# Sheet_2.net
KiCad netlist of a schematic drawn in Altium Designer
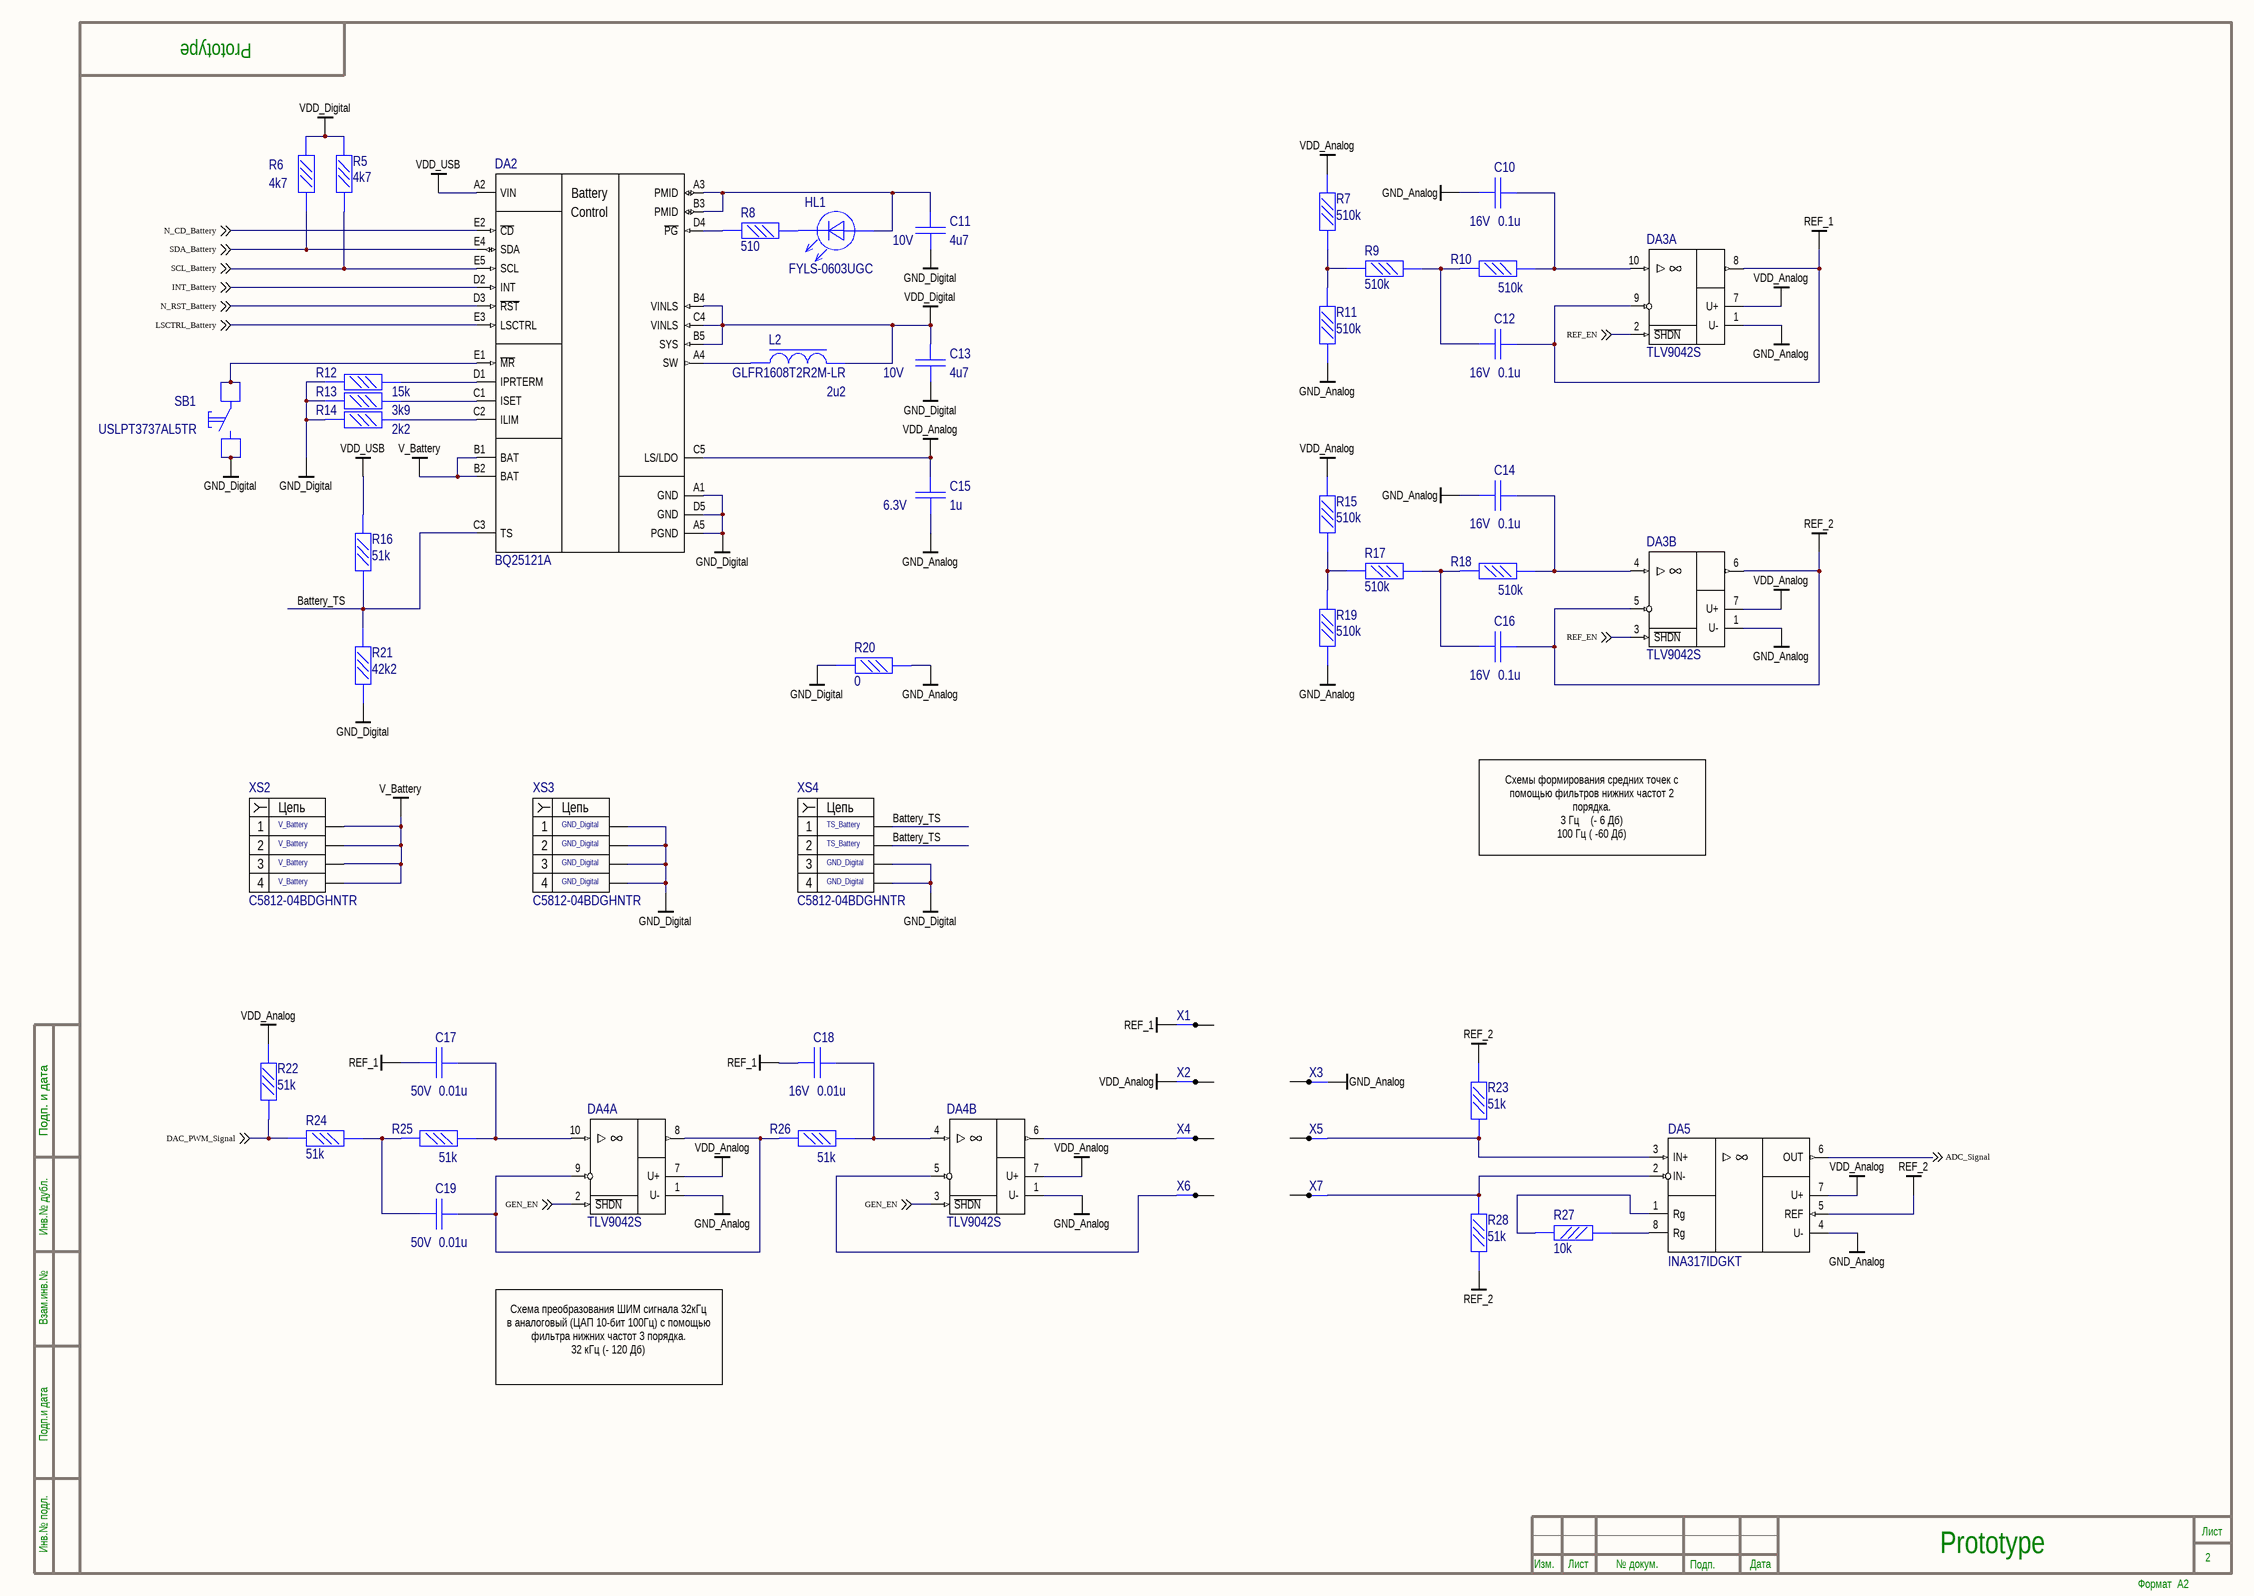
[diagram p0: Sheet_2.SchDoc]

(export (version "E")
  (design (tool "Eeschema 10.0.6"))
  (components
    (comp (ref "C10")
      (value "0.1u")
      (footprint "C0201_2")
      (fields
        (field (name "VOLTAGE") "16V")
        (field (name "Comment") "X7R")
        (field (name "PUBLISHER") "Andrew Danich")
      )
      (libsource (lib "Capacitor GOST") (part "X7R C0201"))
    )
    (comp (ref "C11")
      (value "4u7")
      (footprint "SMD Capacitor:C0603")
      (fields
        (field (name "VOLTAGE") "10V")
        (field (name "Comment") "X7R")
        (field (name "PUBLISHER") "Andrew Danich")
      )
      (libsource (lib "Capacitor GOST") (part "X7R C0603"))
    )
    (comp (ref "C12")
      (value "0.1u")
      (footprint "C0201_2")
      (fields
        (field (name "VOLTAGE") "16V")
        (field (name "Comment") "X7R")
        (field (name "PUBLISHER") "Andrew Danich")
      )
      (libsource (lib "Capacitor GOST") (part "X7R C0201"))
    )
    (comp (ref "C13")
      (value "4u7")
      (footprint "SMD Capacitor:C0603")
      (fields
        (field (name "VOLTAGE") "10V")
        (field (name "Comment") "X7R")
        (field (name "PUBLISHER") "Andrew Danich")
      )
      (libsource (lib "Capacitor GOST") (part "X7R C0603"))
    )
    (comp (ref "C14")
      (value "0.1u")
      (footprint "C0201_2")
      (fields
        (field (name "VOLTAGE") "16V")
        (field (name "Comment") "X7R")
        (field (name "PUBLISHER") "Andrew Danich")
      )
      (libsource (lib "Capacitor GOST") (part "X7R C0201"))
    )
    (comp (ref "C15")
      (value "1u")
      (footprint "SMD Capacitor:C0402")
      (fields
        (field (name "VOLTAGE") "6.3V")
        (field (name "Comment") "X5R")
        (field (name "PUBLISHER") "Andrew Danich")
      )
      (libsource (lib "Capacitor GOST") (part "X5R C0402"))
    )
    (comp (ref "C16")
      (value "0.1u")
      (footprint "C0201_2")
      (fields
        (field (name "VOLTAGE") "16V")
        (field (name "Comment") "X7R")
        (field (name "PUBLISHER") "Andrew Danich")
      )
      (libsource (lib "Capacitor GOST") (part "X7R C0201"))
    )
    (comp (ref "C17")
      (value "0.01u")
      (footprint "C0201_2")
      (fields
        (field (name "VOLTAGE") "50V")
        (field (name "Comment") "X7R")
        (field (name "PUBLISHER") "Andrew Danich")
      )
      (libsource (lib "Capacitor GOST") (part "X7R C0201"))
    )
    (comp (ref "C18")
      (value "0.01u")
      (footprint "C0201_2")
      (fields
        (field (name "VOLTAGE") "16V")
        (field (name "Comment") "X7R")
        (field (name "PUBLISHER") "Andrew Danich")
      )
      (libsource (lib "Capacitor GOST") (part "X7R C0201"))
    )
    (comp (ref "C19")
      (value "0.01u")
      (footprint "C0201_2")
      (fields
        (field (name "VOLTAGE") "50V")
        (field (name "Comment") "X7R")
        (field (name "PUBLISHER") "Andrew Danich")
      )
      (libsource (lib "Capacitor GOST") (part "X7R C0201"))
    )
    (comp (ref "DA2")
      (value "BQ25121A")
      (footprint "SMD WLCSP:dsbga-25")
      (fields (field (name "PUBLISHER") "Andrew Danich"))
      (libsource (lib "Battery Control GOST") (part "BQ25121A"))
    )
    (comp (ref "DA3")
      (value "TLV9042S")
      (footprint "SMD XDFN:X2QFN")
      (fields (field (name "Comment") "TLV9042SIRUGR") (field (name "PUBLISHER") "Andrew Danich"))
      (libsource (lib "OPA GOST") (part "TLV9042SIRUGR"))
    )
    (comp (ref "DA4")
      (value "TLV9042S")
      (footprint "SMD XDFN:X2QFN")
      (fields (field (name "Comment") "TLV9042SIRUGR") (field (name "PUBLISHER") "Andrew Danich"))
      (libsource (lib "OPA GOST") (part "TLV9042SIRUGR"))
    )
    (comp (ref "DA5")
      (value "INA317IDGKT")
      (footprint "SMD VSSOP:VSSOP-8")
      (fields (field (name "PUBLISHER") "Andrew Danich"))
      (libsource (lib "OPA GOST") (part "INA317IDGKT"))
    )
    (comp (ref "HL1")
      (value "FYLS-0603UGC")
      (footprint "SMD Leds:LD0603")
      (fields (field (name "PUBLISHER") "Andrew Danich"))
      (libsource (lib "Led GOST") (part "FYLS-0603UGC"))
    )
    (comp (ref "L2")
      (value "2u2")
      (footprint "SMD Coil:L0603")
      (fields
        (field (name "NAME") "GLFR1608T2R2M-LR")
        (field (name "Comment") "GLFR1608T2R2M-LR")
        (field (name "PUBLISHER") "Andrew Danich")
      )
      (libsource (lib "Coil GOST") (part "GLFR1608T2R2M-LR"))
    )
    (comp (ref "R5")
      (value "4k7")
      (footprint "R0201_2")
      (fields (field (name "Comment") "ERJ1GN") (field (name "PUBLISHER") "Andrew Danich"))
      (libsource (lib "Resistor GOST") (part "R0201"))
    )
    (comp (ref "R6")
      (value "4k7")
      (footprint "R0201_2")
      (fields (field (name "Comment") "ERJ1GN") (field (name "PUBLISHER") "Andrew Danich"))
      (libsource (lib "Resistor GOST") (part "R0201"))
    )
    (comp (ref "R7")
      (value "510k")
      (footprint "R0201_2")
      (fields (field (name "Comment") "ERJ1GN") (field (name "PUBLISHER") "Andrew Danich"))
      (libsource (lib "Resistor GOST") (part "R0201"))
    )
    (comp (ref "R8")
      (value "510")
      (footprint "R0201_2")
      (fields (field (name "Comment") "ERJ1GN") (field (name "PUBLISHER") "Andrew Danich"))
      (libsource (lib "Resistor GOST") (part "R0201"))
    )
    (comp (ref "R9")
      (value "510k")
      (footprint "R0201_2")
      (fields (field (name "Comment") "ERJ1GN") (field (name "PUBLISHER") "Andrew Danich"))
      (libsource (lib "Resistor GOST") (part "R0201"))
    )
    (comp (ref "R10")
      (value "510k")
      (footprint "R0201_2")
      (fields (field (name "Comment") "ERJ1GN") (field (name "PUBLISHER") "Andrew Danich"))
      (libsource (lib "Resistor GOST") (part "R0201"))
    )
    (comp (ref "R11")
      (value "510k")
      (footprint "R0201_2")
      (fields (field (name "Comment") "ERJ1GN") (field (name "PUBLISHER") "Andrew Danich"))
      (libsource (lib "Resistor GOST") (part "R0201"))
    )
    (comp (ref "R12")
      (value "15k")
      (footprint "R0201_2")
      (fields (field (name "Comment") "ERJ1GN") (field (name "PUBLISHER") "Andrew Danich"))
      (libsource (lib "Resistor GOST") (part "R0201"))
    )
    (comp (ref "R13")
      (value "3k9")
      (footprint "R0201_2")
      (fields (field (name "Comment") "ERJ1GN") (field (name "PUBLISHER") "Andrew Danich"))
      (libsource (lib "Resistor GOST") (part "R0201"))
    )
    (comp (ref "R14")
      (value "2k2")
      (footprint "R0201_2")
      (fields (field (name "Comment") "ERJ1GN") (field (name "PUBLISHER") "Andrew Danich"))
      (libsource (lib "Resistor GOST") (part "R0201"))
    )
    (comp (ref "R15")
      (value "510k")
      (footprint "R0201_2")
      (fields (field (name "Comment") "ERJ1GN") (field (name "PUBLISHER") "Andrew Danich"))
      (libsource (lib "Resistor GOST") (part "R0201"))
    )
    (comp (ref "R16")
      (value "51k")
      (footprint "R0201_2")
      (fields (field (name "Comment") "ERJ1GN") (field (name "PUBLISHER") "Andrew Danich"))
      (libsource (lib "Resistor GOST") (part "R0201"))
    )
    (comp (ref "R17")
      (value "510k")
      (footprint "R0201_2")
      (fields (field (name "Comment") "ERJ1GN") (field (name "PUBLISHER") "Andrew Danich"))
      (libsource (lib "Resistor GOST") (part "R0201"))
    )
    (comp (ref "R18")
      (value "510k")
      (footprint "R0201_2")
      (fields (field (name "Comment") "ERJ1GN") (field (name "PUBLISHER") "Andrew Danich"))
      (libsource (lib "Resistor GOST") (part "R0201"))
    )
    (comp (ref "R19")
      (value "510k")
      (footprint "R0201_2")
      (fields (field (name "Comment") "ERJ1GN") (field (name "PUBLISHER") "Andrew Danich"))
      (libsource (lib "Resistor GOST") (part "R0201"))
    )
    (comp (ref "R20")
      (value "0")
      (footprint "R0201_2")
      (fields (field (name "Comment") "ERJ1GN") (field (name "PUBLISHER") "Andrew Danich"))
      (libsource (lib "Resistor GOST") (part "R0201"))
    )
    (comp (ref "R21")
      (value "42k2")
      (footprint "R0201_2")
      (fields (field (name "Comment") "ERJ1GN") (field (name "PUBLISHER") "Andrew Danich"))
      (libsource (lib "Resistor GOST") (part "R0201"))
    )
    (comp (ref "R22")
      (value "51k")
      (footprint "R0201_2")
      (fields (field (name "Comment") "ERJ1GN") (field (name "PUBLISHER") "Andrew Danich"))
      (libsource (lib "Resistor GOST") (part "R0201"))
    )
    (comp (ref "R23")
      (value "51k")
      (footprint "R0201_2")
      (fields (field (name "Comment") "ERJ1GN") (field (name "PUBLISHER") "Andrew Danich"))
      (libsource (lib "Resistor GOST") (part "R0201"))
    )
    (comp (ref "R24")
      (value "51k")
      (footprint "R0201_2")
      (fields (field (name "Comment") "ERJ1GN") (field (name "PUBLISHER") "Andrew Danich"))
      (libsource (lib "Resistor GOST") (part "R0201"))
    )
    (comp (ref "R25")
      (value "51k")
      (footprint "R0201_2")
      (fields (field (name "Comment") "ERJ1GN") (field (name "PUBLISHER") "Andrew Danich"))
      (libsource (lib "Resistor GOST") (part "R0201"))
    )
    (comp (ref "R26")
      (value "51k")
      (footprint "R0201_2")
      (fields (field (name "Comment") "ERJ1GN") (field (name "PUBLISHER") "Andrew Danich"))
      (libsource (lib "Resistor GOST") (part "R0201"))
    )
    (comp (ref "R27")
      (value "10k")
      (footprint "R0201_2")
      (fields (field (name "Comment") "ERJ1GN") (field (name "PUBLISHER") "Andrew Danich"))
      (libsource (lib "Resistor GOST") (part "R0201"))
    )
    (comp (ref "R28")
      (value "51k")
      (footprint "R0201_2")
      (fields (field (name "Comment") "ERJ1GN") (field (name "PUBLISHER") "Andrew Danich"))
      (libsource (lib "Resistor GOST") (part "R0201"))
    )
    (comp (ref "SB1")
      (value "USLPT3737AL5TR")
      (footprint "SMD Button:USLPT3737AL5TR")
      (fields (field (name "PUBLISHER") "Andrew Danich"))
      (libsource (lib "Button GOST") (part "USLPT3737AL5TR"))
    )
    (comp (ref "X1")
      (value "Contact")
      (footprint "SMD Connector:TEST_PIN_2")
      (fields (field (name "PUBLISHER") "Andrew Danich"))
      (libsource (lib "Connector GOST") (part "Contact"))
    )
    (comp (ref "X2")
      (value "Contact")
      (footprint "SMD Connector:TEST_PIN_2")
      (fields (field (name "PUBLISHER") "Andrew Danich"))
      (libsource (lib "Connector GOST") (part "Contact"))
    )
    (comp (ref "X3")
      (value "Contact")
      (footprint "SMD Connector:TEST_PIN_2")
      (fields (field (name "PUBLISHER") "Andrew Danich"))
      (libsource (lib "Connector GOST") (part "Contact"))
    )
    (comp (ref "X4")
      (value "Contact")
      (footprint "SMD Connector:TEST_PIN_2")
      (fields (field (name "PUBLISHER") "Andrew Danich"))
      (libsource (lib "Connector GOST") (part "Contact"))
    )
    (comp (ref "X5")
      (value "Contact")
      (footprint "SMD Connector:TEST_PIN_2")
      (fields (field (name "PUBLISHER") "Andrew Danich"))
      (libsource (lib "Connector GOST") (part "Contact"))
    )
    (comp (ref "X6")
      (value "Contact")
      (footprint "SMD Connector:TEST_PIN_2")
      (fields (field (name "PUBLISHER") "Andrew Danich"))
      (libsource (lib "Connector GOST") (part "Contact"))
    )
    (comp (ref "X7")
      (value "Contact")
      (footprint "SMD Connector:TEST_PIN_2")
      (fields (field (name "PUBLISHER") "Andrew Danich"))
      (libsource (lib "Connector GOST") (part "Contact"))
    )
    (comp (ref "XS2")
      (value "C5812-04BDGHNTR")
      (footprint "SMD Connector:C5812-04")
      (fields
        (field (name "1_LINE") "V_Battery")
        (field (name "2_LINE") "V_Battery")
        (field (name "3_LINE") "V_Battery")
        (field (name "4_LINE") "V_Battery")
        (field (name "PUBLISHER") "Andrew Danich")
      )
      (libsource (lib "Connector GOST") (part "C5812-04BDGHNTR"))
    )
    (comp (ref "XS3")
      (value "C5812-04BDGHNTR")
      (footprint "SMD Connector:C5812-04")
      (fields
        (field (name "1_LINE") "GND_Digital")
        (field (name "2_LINE") "GND_Digital")
        (field (name "3_LINE") "GND_Digital")
        (field (name "4_LINE") "GND_Digital")
        (field (name "PUBLISHER") "Andrew Danich")
      )
      (libsource (lib "Connector GOST") (part "C5812-04BDGHNTR"))
    )
    (comp (ref "XS4")
      (value "C5812-04BDGHNTR")
      (footprint "SMD Connector:C5812-04")
      (fields
        (field (name "1_LINE") "TS_Battery")
        (field (name "2_LINE") "TS_Battery")
        (field (name "3_LINE") "GND_Digital")
        (field (name "4_LINE") "GND_Digital")
        (field (name "PUBLISHER") "Andrew Danich")
      )
      (libsource (lib "Connector GOST") (part "C5812-04BDGHNTR"))
    )
  )
  (nets
    (net (code "1") (name "/Battery_TS") (class "Default")
      (node (ref "DA2") (pin "C3") (pinfunction "TS_C3") (pintype "power_in"))
      (node (ref "R16") (pin "1") (pinfunction "1_1") (pintype "passive"))
      (node (ref "R21") (pin "2") (pinfunction "2_2") (pintype "passive"))
      (node (ref "XS4") (pin "1") (pintype "passive"))
      (node (ref "XS4") (pin "2") (pintype "passive"))
    )
    (net (code "2") (name "ADC_Signal") (class "Default")
      (node (ref "DA5") (pin "6") (pinfunction "OUT_6") (pintype "output"))
    )
    (net (code "3") (name "DAC_PWM_Signal") (class "Default")
      (node (ref "R22") (pin "1") (pinfunction "1_1") (pintype "passive"))
      (node (ref "R24") (pin "1") (pinfunction "1_1") (pintype "passive"))
    )
    (net (code "4") (name "GEN_EN") (class "Default")
      (node (ref "DA4") (pin "2") (pinfunction "~{SHDN}_2") (pintype "input"))
      (node (ref "DA4") (pin "3") (pinfunction "~{SHDN}_3") (pintype "input"))
    )
    (net (code "5") (name "GND_Analog") (class "Default")
      (node (ref "C10") (pin "1") (pinfunction "1_1") (pintype "passive"))
      (node (ref "C14") (pin "1") (pinfunction "1_1") (pintype "passive"))
      (node (ref "C15") (pin "2") (pinfunction "2_2") (pintype "passive"))
      (node (ref "DA3") (pin "1") (pinfunction "U-_1") (pintype "power_in"))
      (node (ref "DA4") (pin "1") (pinfunction "U-_1") (pintype "power_in"))
      (node (ref "DA5") (pin "4") (pinfunction "U-_4") (pintype "power_in"))
      (node (ref "R11") (pin "1") (pinfunction "1_1") (pintype "passive"))
      (node (ref "R19") (pin "1") (pinfunction "1_1") (pintype "passive"))
      (node (ref "R20") (pin "2") (pinfunction "2_2") (pintype "passive"))
      (node (ref "X3") (pin "1") (pintype "passive"))
    )
    (net (code "6") (name "GND_Digital") (class "Default")
      (node (ref "C11") (pin "2") (pinfunction "2_2") (pintype "passive"))
      (node (ref "C13") (pin "2") (pinfunction "2_2") (pintype "passive"))
      (node (ref "DA2") (pin "A1") (pinfunction "GND_A1") (pintype "power_in"))
      (node (ref "DA2") (pin "A5") (pinfunction "PGND_A5") (pintype "power_in"))
      (node (ref "DA2") (pin "D5") (pinfunction "GND_D5") (pintype "power_in"))
      (node (ref "R12") (pin "1") (pinfunction "1_1") (pintype "passive"))
      (node (ref "R13") (pin "1") (pinfunction "1_1") (pintype "passive"))
      (node (ref "R14") (pin "1") (pinfunction "1_1") (pintype "passive"))
      (node (ref "R20") (pin "1") (pinfunction "1_1") (pintype "passive"))
      (node (ref "R21") (pin "1") (pinfunction "1_1") (pintype "passive"))
      (node (ref "SB1") (pin "2") (pintype "passive"))
      (node (ref "SB1") (pin "4") (pintype "passive"))
      (node (ref "XS3") (pin "1") (pintype "passive"))
      (node (ref "XS3") (pin "2") (pintype "passive"))
      (node (ref "XS3") (pin "3") (pintype "passive"))
      (node (ref "XS3") (pin "4") (pintype "passive"))
      (node (ref "XS4") (pin "3") (pintype "passive"))
      (node (ref "XS4") (pin "4") (pintype "passive"))
    )
    (net (code "7") (name "INT_Battery") (class "Default")
      (node (ref "DA2") (pin "D2") (pinfunction "INT_D2") (pintype "input"))
    )
    (net (code "8") (name "LSCTRL_Battery") (class "Default")
      (node (ref "DA2") (pin "E3") (pinfunction "LSCTRL_E3") (pintype "input"))
    )
    (net (code "9") (name "N_CD_Battery") (class "Default")
      (node (ref "DA2") (pin "E2") (pinfunction "~{CD}_E2") (pintype "input"))
    )
    (net (code "10") (name "N_RST_Battery") (class "Default")
      (node (ref "DA2") (pin "D3") (pinfunction "~{RST}_D3") (pintype "input"))
    )
    (net (code "11") (name "Net-(C12-Pad1)") (class "Default")
      (node (ref "C12") (pin "1") (pinfunction "1_1") (pintype "passive"))
      (node (ref "R10") (pin "1") (pinfunction "1_1") (pintype "passive"))
      (node (ref "R9") (pin "2") (pinfunction "2_2") (pintype "passive"))
    )
    (net (code "12") (name "Net-(C16-Pad1)") (class "Default")
      (node (ref "C16") (pin "1") (pinfunction "1_1") (pintype "passive"))
      (node (ref "R17") (pin "2") (pinfunction "2_2") (pintype "passive"))
      (node (ref "R18") (pin "1") (pinfunction "1_1") (pintype "passive"))
    )
    (net (code "13") (name "Net-(C19-Pad1)") (class "Default")
      (node (ref "C19") (pin "1") (pinfunction "1_1") (pintype "passive"))
      (node (ref "R24") (pin "2") (pinfunction "2_2") (pintype "passive"))
      (node (ref "R25") (pin "1") (pinfunction "1_1") (pintype "passive"))
    )
    (net (code "14") (name "Net-(DA2-ILIM)") (class "Default")
      (node (ref "DA2") (pin "C2") (pinfunction "ILIM_C2") (pintype "passive"))
      (node (ref "R14") (pin "2") (pinfunction "2_2") (pintype "passive"))
    )
    (net (code "15") (name "Net-(DA2-IPRTERM)") (class "Default")
      (node (ref "DA2") (pin "D1") (pinfunction "IPRTERM_D1") (pintype "passive"))
      (node (ref "R12") (pin "2") (pinfunction "2_2") (pintype "passive"))
    )
    (net (code "16") (name "Net-(DA2-ISET)") (class "Default")
      (node (ref "DA2") (pin "C1") (pinfunction "ISET_C1") (pintype "passive"))
      (node (ref "R13") (pin "2") (pinfunction "2_2") (pintype "passive"))
    )
    (net (code "17") (name "Net-(DA2-SW)") (class "Default")
      (node (ref "DA2") (pin "A4") (pinfunction "SW_A4") (pintype "output"))
      (node (ref "L2") (pin "1") (pinfunction "1_1") (pintype "passive"))
    )
    (net (code "18") (name "Net-(DA2-~{MR})") (class "Default")
      (node (ref "DA2") (pin "E1") (pinfunction "~{MR}_E1") (pintype "input"))
      (node (ref "SB1") (pin "1") (pintype "passive"))
      (node (ref "SB1") (pin "3") (pintype "passive"))
    )
    (net (code "19") (name "Net-(DA2-~{PG})") (class "Default")
      (node (ref "DA2") (pin "D4") (pinfunction "~{PG}_D4") (pintype "input"))
      (node (ref "R8") (pin "1") (pinfunction "1_1") (pintype "passive"))
    )
    (net (code "20") (name "Net-(DA3A-IN+)") (class "Default")
      (node (ref "C10") (pin "2") (pinfunction "2_2") (pintype "passive"))
      (node (ref "DA3") (pin "10") (pinfunction "IN+_10") (pintype "input"))
      (node (ref "R10") (pin "2") (pinfunction "2_2") (pintype "passive"))
    )
    (net (code "21") (name "Net-(DA3B-IN+)") (class "Default")
      (node (ref "C14") (pin "2") (pinfunction "2_2") (pintype "passive"))
      (node (ref "DA3") (pin "4") (pinfunction "IN+_4") (pintype "input"))
      (node (ref "R18") (pin "2") (pinfunction "2_2") (pintype "passive"))
    )
    (net (code "22") (name "Net-(DA4A-IN+)") (class "Default")
      (node (ref "C17") (pin "2") (pinfunction "2_2") (pintype "passive"))
      (node (ref "DA4") (pin "10") (pinfunction "IN+_10") (pintype "input"))
      (node (ref "R25") (pin "2") (pinfunction "2_2") (pintype "passive"))
    )
    (net (code "23") (name "Net-(DA4A-IN-)") (class "Default")
      (node (ref "C19") (pin "2") (pinfunction "2_2") (pintype "passive"))
      (node (ref "DA4") (pin "8") (pinfunction "OUT_8") (pintype "output"))
      (node (ref "DA4") (pin "9") (pinfunction "IN-_9") (pintype "input"))
      (node (ref "R26") (pin "1") (pinfunction "1_1") (pintype "passive"))
    )
    (net (code "24") (name "Net-(DA4B-IN+)") (class "Default")
      (node (ref "C18") (pin "2") (pinfunction "2_2") (pintype "passive"))
      (node (ref "DA4") (pin "4") (pinfunction "IN+_4") (pintype "input"))
      (node (ref "R26") (pin "2") (pinfunction "2_2") (pintype "passive"))
    )
    (net (code "25") (name "Net-(DA4B-IN-)") (class "Default")
      (node (ref "DA4") (pin "5") (pinfunction "IN-_5") (pintype "input"))
      (node (ref "X6") (pin "1") (pintype "passive"))
    )
    (net (code "26") (name "Net-(DA4B-OUT)") (class "Default")
      (node (ref "DA4") (pin "6") (pinfunction "OUT_6") (pintype "output"))
      (node (ref "X4") (pin "1") (pintype "passive"))
    )
    (net (code "27") (name "Net-(DA5-IN+)") (class "Default")
      (node (ref "DA5") (pin "3") (pinfunction "IN+_3") (pintype "input"))
      (node (ref "R23") (pin "1") (pinfunction "1_1") (pintype "passive"))
      (node (ref "X5") (pin "1") (pintype "passive"))
    )
    (net (code "28") (name "Net-(DA5-IN-)") (class "Default")
      (node (ref "DA5") (pin "2") (pinfunction "IN-_2") (pintype "input"))
      (node (ref "R28") (pin "2") (pinfunction "2_2") (pintype "passive"))
      (node (ref "X7") (pin "1") (pintype "passive"))
    )
    (net (code "29") (name "Net-(DA5-Rg-Pad1)") (class "Default")
      (node (ref "DA5") (pin "1") (pinfunction "Rg_1") (pintype "passive"))
      (node (ref "R27") (pin "2") (pinfunction "2_2") (pintype "passive"))
    )
    (net (code "30") (name "Net-(DA5-Rg-Pad8)") (class "Default")
      (node (ref "DA5") (pin "8") (pinfunction "Rg_8") (pintype "passive"))
      (node (ref "R27") (pin "1") (pinfunction "1_1") (pintype "passive"))
    )
    (net (code "31") (name "Net-(HL1-А)") (class "Default")
      (node (ref "C11") (pin "1") (pinfunction "1_1") (pintype "passive"))
      (node (ref "DA2") (pin "A3") (pinfunction "PMID_A3") (pintype "bidirectional"))
      (node (ref "DA2") (pin "B3") (pinfunction "PMID_B3") (pintype "bidirectional"))
      (node (ref "HL1") (pin "1") (pinfunction "А_1") (pintype "passive"))
    )
    (net (code "32") (name "Net-(HL1-К)") (class "Default")
      (node (ref "HL1") (pin "2") (pinfunction "К_2") (pintype "passive"))
      (node (ref "R8") (pin "2") (pinfunction "2_2") (pintype "passive"))
    )
    (net (code "33") (name "Net-(R11-Pad2)") (class "Default")
      (node (ref "R11") (pin "2") (pinfunction "2_2") (pintype "passive"))
      (node (ref "R7") (pin "1") (pinfunction "1_1") (pintype "passive"))
      (node (ref "R9") (pin "1") (pinfunction "1_1") (pintype "passive"))
    )
    (net (code "34") (name "Net-(R15-Pad1)") (class "Default")
      (node (ref "R15") (pin "1") (pinfunction "1_1") (pintype "passive"))
      (node (ref "R17") (pin "1") (pinfunction "1_1") (pintype "passive"))
      (node (ref "R19") (pin "2") (pinfunction "2_2") (pintype "passive"))
    )
    (net (code "35") (name "REF_1") (class "Default")
      (node (ref "C12") (pin "2") (pinfunction "2_2") (pintype "passive"))
      (node (ref "C17") (pin "1") (pinfunction "1_1") (pintype "passive"))
      (node (ref "C18") (pin "1") (pinfunction "1_1") (pintype "passive"))
      (node (ref "DA3") (pin "8") (pinfunction "OUT_8") (pintype "output"))
      (node (ref "DA3") (pin "9") (pinfunction "IN-_9") (pintype "input"))
      (node (ref "X1") (pin "1") (pintype "passive"))
    )
    (net (code "36") (name "REF_2") (class "Default")
      (node (ref "C16") (pin "2") (pinfunction "2_2") (pintype "passive"))
      (node (ref "DA3") (pin "5") (pinfunction "IN-_5") (pintype "input"))
      (node (ref "DA3") (pin "6") (pinfunction "OUT_6") (pintype "output"))
      (node (ref "DA5") (pin "5") (pinfunction "REF_5") (pintype "input"))
      (node (ref "R23") (pin "2") (pinfunction "2_2") (pintype "passive"))
      (node (ref "R28") (pin "1") (pinfunction "1_1") (pintype "passive"))
    )
    (net (code "37") (name "REF_EN") (class "Default")
      (node (ref "DA3") (pin "2") (pinfunction "~{SHDN}_2") (pintype "input"))
      (node (ref "DA3") (pin "3") (pinfunction "~{SHDN}_3") (pintype "input"))
    )
    (net (code "38") (name "SCL_Battery") (class "Default")
      (node (ref "DA2") (pin "E5") (pinfunction "SCL_E5") (pintype "input"))
      (node (ref "R5") (pin "1") (pinfunction "1_1") (pintype "passive"))
    )
    (net (code "39") (name "SDA_Battery") (class "Default")
      (node (ref "DA2") (pin "E4") (pinfunction "SDA_E4") (pintype "bidirectional"))
      (node (ref "R6") (pin "1") (pinfunction "1_1") (pintype "passive"))
    )
    (net (code "40") (name "VDD_Analog") (class "Default")
      (node (ref "C15") (pin "1") (pinfunction "1_1") (pintype "passive"))
      (node (ref "DA2") (pin "C5") (pinfunction "LS/LDO_C5") (pintype "power_in"))
      (node (ref "DA3") (pin "7") (pinfunction "U+_7") (pintype "power_in"))
      (node (ref "DA4") (pin "7") (pinfunction "U+_7") (pintype "power_in"))
      (node (ref "DA5") (pin "7") (pinfunction "U+_7") (pintype "power_in"))
      (node (ref "R15") (pin "2") (pinfunction "2_2") (pintype "passive"))
      (node (ref "R22") (pin "2") (pinfunction "2_2") (pintype "passive"))
      (node (ref "R7") (pin "2") (pinfunction "2_2") (pintype "passive"))
      (node (ref "X2") (pin "1") (pintype "passive"))
    )
    (net (code "41") (name "VDD_Digital") (class "Default")
      (node (ref "C13") (pin "1") (pinfunction "1_1") (pintype "passive"))
      (node (ref "DA2") (pin "B4") (pinfunction "VINLS_B4") (pintype "input"))
      (node (ref "DA2") (pin "B5") (pinfunction "SYS_B5") (pintype "input"))
      (node (ref "DA2") (pin "C4") (pinfunction "VINLS_C4") (pintype "input"))
      (node (ref "L2") (pin "2") (pinfunction "2_2") (pintype "passive"))
      (node (ref "R5") (pin "2") (pinfunction "2_2") (pintype "passive"))
      (node (ref "R6") (pin "2") (pinfunction "2_2") (pintype "passive"))
    )
    (net (code "42") (name "VDD_USB") (class "Default")
      (node (ref "DA2") (pin "A2") (pinfunction "VIN_A2") (pintype "power_in"))
      (node (ref "R16") (pin "2") (pinfunction "2_2") (pintype "passive"))
    )
    (net (code "43") (name "V_Battery") (class "Default")
      (node (ref "DA2") (pin "B1") (pinfunction "BAT_B1") (pintype "power_in"))
      (node (ref "DA2") (pin "B2") (pinfunction "BAT_B2") (pintype "power_in"))
      (node (ref "XS2") (pin "1") (pintype "passive"))
      (node (ref "XS2") (pin "2") (pintype "passive"))
      (node (ref "XS2") (pin "3") (pintype "passive"))
      (node (ref "XS2") (pin "4") (pintype "passive"))
    )
  )
)
